# 2_ETH.net
KiCad netlist of a schematic drawn in Altium Designer
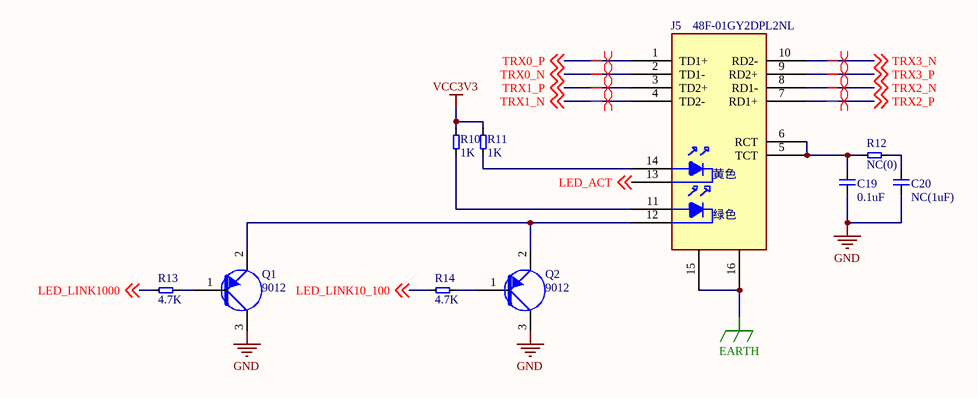
[diagram p0: 2.ETH.SchDoc]

(export (version "E")
  (design (tool "Eeschema 10.0.6"))
  (components
    (comp (ref "C19")
      (value "0.1uF")
      (footprint "0603C")
      (description "电容")
      (libsource (lib "LDT-SCH") (part "电容"))
    )
    (comp (ref "C20")
      (value "NC(1uF)")
      (footprint "0603C")
      (description "电容")
      (libsource (lib "LDT-SCH") (part "电容"))
    )
    (comp (ref "J5")
      (value "48F-01GY2DPL2NL")
      (footprint "RJ45C-48F-01GY2DPL2NL")
      (libsource (lib "LDT-SCH") (part "48F-01GY2DPL2NL"))
    )
    (comp (ref "Q1") (value "9012") (footprint "SOT-23-PMOS") (libsource (lib "LDT-SCH") (part "9012")))
    (comp (ref "Q2") (value "9012") (footprint "SOT-23-PMOS") (libsource (lib "LDT-SCH") (part "9012")))
    (comp (ref "R10")
      (value "1K")
      (footprint "0603R")
      (description "电阻")
      (libsource (lib "LDT-SCH") (part "电阻"))
    )
    (comp (ref "R11")
      (value "1K")
      (footprint "0603R")
      (description "电阻")
      (libsource (lib "LDT-SCH") (part "电阻"))
    )
    (comp (ref "R12")
      (value "NC(0)")
      (footprint "0603R")
      (description "电阻")
      (libsource (lib "LDT-SCH") (part "电阻"))
    )
    (comp (ref "R13")
      (value "4.7K")
      (footprint "0603R")
      (description "电阻")
      (libsource (lib "LDT-SCH") (part "电阻"))
    )
    (comp (ref "R14")
      (value "4.7K")
      (footprint "0603R")
      (description "电阻")
      (libsource (lib "LDT-SCH") (part "电阻"))
    )
  )
  (nets
    (net (code "1") (name "EARTH") (class "Default")
      (node (ref "J5") (pin "15") (pinfunction "15_15") (pintype "passive"))
      (node (ref "J5") (pin "16") (pinfunction "16_16") (pintype "passive"))
    )
    (net (code "2") (name "GND") (class "Default")
      (node (ref "C19") (pin "2") (pintype "passive"))
      (node (ref "C20") (pin "1") (pintype "passive"))
      (node (ref "Q1") (pin "3") (pintype "passive"))
      (node (ref "Q2") (pin "3") (pintype "passive"))
    )
    (net (code "3") (name "LED_ACT") (class "Default")
      (node (ref "J5") (pin "13") (pinfunction "13_13") (pintype "passive"))
    )
    (net (code "4") (name "LED_LINK10_100") (class "Default")
      (node (ref "R14") (pin "2") (pintype "passive"))
    )
    (net (code "5") (name "LED_LINK1000") (class "Default") (node (ref "R13") (pin "2") (pintype "passive")))
    (net (code "6") (name "Net-(C20-Pad2)") (class "Default")
      (node (ref "C20") (pin "2") (pintype "passive"))
      (node (ref "R12") (pin "1") (pintype "passive"))
    )
    (net (code "7") (name "Net-(J5-Pad11)") (class "Default")
      (node (ref "J5") (pin "11") (pinfunction "11_11") (pintype "passive"))
      (node (ref "R10") (pin "1") (pintype "passive"))
    )
    (net (code "8") (name "Net-(J5-Pad12)") (class "Default")
      (node (ref "J5") (pin "12") (pinfunction "12_12") (pintype "passive"))
      (node (ref "Q1") (pin "2") (pintype "passive"))
      (node (ref "Q2") (pin "2") (pintype "passive"))
    )
    (net (code "9") (name "Net-(J5-Pad14)") (class "Default")
      (node (ref "J5") (pin "14") (pinfunction "14_14") (pintype "passive"))
      (node (ref "R11") (pin "1") (pintype "passive"))
    )
    (net (code "10") (name "Net-(J5-RCT)") (class "Default")
      (node (ref "C19") (pin "1") (pintype "passive"))
      (node (ref "J5") (pin "5") (pinfunction "TCT_5") (pintype "passive"))
      (node (ref "J5") (pin "6") (pinfunction "RCT_6") (pintype "passive"))
      (node (ref "R12") (pin "2") (pintype "passive"))
    )
    (net (code "11") (name "Net-(Q1-Pad1)") (class "Default")
      (node (ref "Q1") (pin "1") (pintype "passive"))
      (node (ref "R13") (pin "1") (pintype "passive"))
    )
    (net (code "12") (name "Net-(Q2-Pad1)") (class "Default")
      (node (ref "Q2") (pin "1") (pintype "passive"))
      (node (ref "R14") (pin "1") (pintype "passive"))
    )
    (net (code "13") (name "TRX0_N") (class "Default")
      (node (ref "J5") (pin "2") (pinfunction "TD1-_2") (pintype "passive"))
    )
    (net (code "14") (name "TRX0_P") (class "Default")
      (node (ref "J5") (pin "1") (pinfunction "TD1+_1") (pintype "passive"))
    )
    (net (code "15") (name "TRX1_N") (class "Default")
      (node (ref "J5") (pin "4") (pinfunction "TD2-_4") (pintype "passive"))
    )
    (net (code "16") (name "TRX1_P") (class "Default")
      (node (ref "J5") (pin "3") (pinfunction "TD2+_3") (pintype "passive"))
    )
    (net (code "17") (name "TRX2_N") (class "Default")
      (node (ref "J5") (pin "8") (pinfunction "RD1-_8") (pintype "passive"))
    )
    (net (code "18") (name "TRX2_P") (class "Default")
      (node (ref "J5") (pin "7") (pinfunction "RD1+_7") (pintype "passive"))
    )
    (net (code "19") (name "TRX3_N") (class "Default")
      (node (ref "J5") (pin "10") (pinfunction "RD2-_10") (pintype "passive"))
    )
    (net (code "20") (name "TRX3_P") (class "Default")
      (node (ref "J5") (pin "9") (pinfunction "RD2+_9") (pintype "passive"))
    )
    (net (code "21") (name "VCC3V3") (class "Default")
      (node (ref "R10") (pin "2") (pintype "passive"))
      (node (ref "R11") (pin "2") (pintype "passive"))
    )
  )
)
